# 09-General_I2C_Devices.net
KiCad netlist of a schematic drawn in Altium Designer
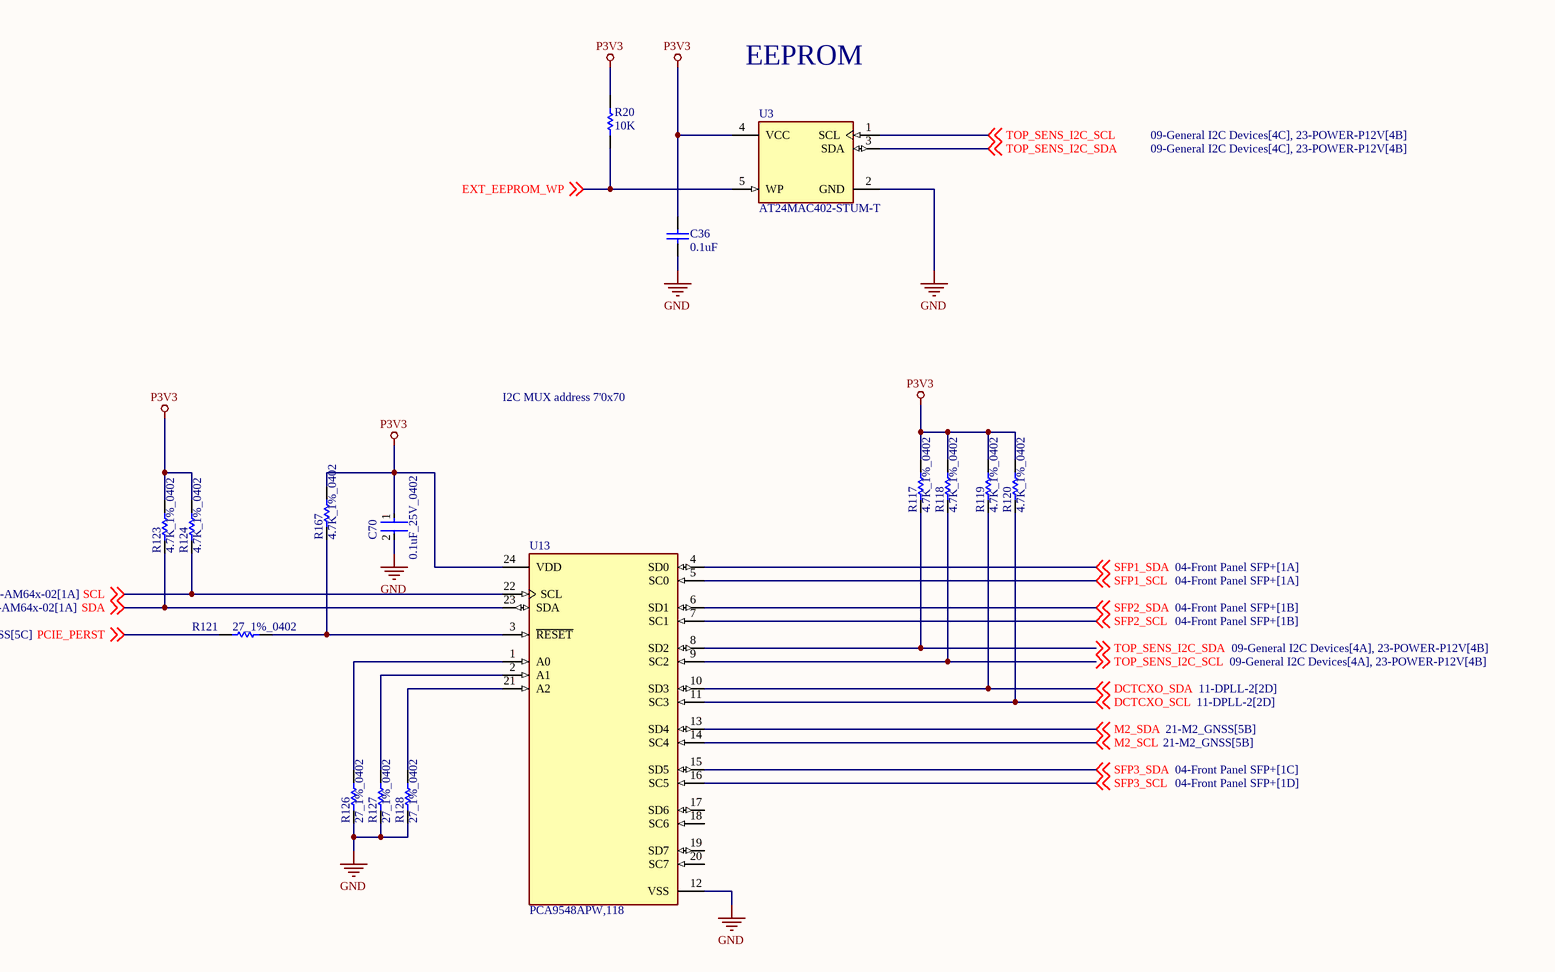
[diagram p0: 09-General I2C Devices.SchDoc]

(export (version "E")
  (design (tool "Eeschema 10.0.6"))
  (components
    (comp (ref "C36")
      (value "0.1uF")
      (footprint "CAPC1608X87X45ML20T05")
      (description "C0603X104K5RACAUTO")
      (fields (field (name "MANUFACTURER") "Kemet"))
      (libsource (lib "Altium Content Vault") (part "CAP"))
    )
    (comp (ref "C70")
      (value "0.1uF_25V_0402")
      (footprint "FP-0402-L_1_0_1-W_0_5_0_1-IPC_C")
      (description "General Purpose Ceramic Capacitor, 0402, 100nF, 10%, X7R, 15%, 25V")
      (fields (field (name "VOLTAGE") "25V") (field (name "TOLERANCE") "10%"))
      (libsource (lib "Altium Content Vault") (part "b4654b650e69147ec39a6b967a45e02"))
    )
    (comp (ref "R20")
      (value "10K")
      (footprint "RESC1608X55X30LL15T20")
      (fields (field (name "TOLERANCE") "±1%") (field (name "MANUFACTURER") "Stackpole-Electronics-Inc."))
      (libsource (lib "Altium Content Vault") (part "RES-2"))
    )
    (comp (ref "R117")
      (value "4.7K_1%_0402")
      (footprint "RESC1005X40X25NL10T10")
      (fields (field (name "MANUFACTURER") "Bourns") (field (name "PART NUMBER") "CR0402-FX-4701GLF"))
      (libsource (lib "Altium Content Vault") (part "RES"))
    )
    (comp (ref "R118")
      (value "4.7K_1%_0402")
      (footprint "RESC1005X40X25NL10T10")
      (fields (field (name "MANUFACTURER") "Bourns") (field (name "PART NUMBER") "CR0402-FX-4701GLF"))
      (libsource (lib "Altium Content Vault") (part "RES"))
    )
    (comp (ref "R119")
      (value "4.7K_1%_0402")
      (footprint "RESC1005X40X25NL10T10")
      (fields (field (name "MANUFACTURER") "Bourns") (field (name "PART NUMBER") "CR0402-FX-4701GLF"))
      (libsource (lib "Altium Content Vault") (part "RES"))
    )
    (comp (ref "R120")
      (value "4.7K_1%_0402")
      (footprint "RESC1005X40X25NL10T10")
      (fields (field (name "MANUFACTURER") "Bourns") (field (name "PART NUMBER") "CR0402-FX-4701GLF"))
      (libsource (lib "Altium Content Vault") (part "RES"))
    )
    (comp (ref "R121")
      (value "27_1%_0402")
      (footprint "RESC1005X40X25NL05T05")
      (fields (field (name "PART NUMBER") "CRCW040227R0FKED") (field (name "MANUFACTURER") "Vishay Dale"))
      (libsource (lib "Altium Content Vault") (part "RES"))
    )
    (comp (ref "R123")
      (value "4.7K_1%_0402")
      (footprint "RESC1005X40X25NL10T10")
      (fields (field (name "MANUFACTURER") "Bourns") (field (name "PART NUMBER") "CR0402-FX-4701GLF"))
      (libsource (lib "Altium Content Vault") (part "RES"))
    )
    (comp (ref "R124")
      (value "4.7K_1%_0402")
      (footprint "RESC1005X40X25NL10T10")
      (fields (field (name "MANUFACTURER") "Bourns") (field (name "PART NUMBER") "CR0402-FX-4701GLF"))
      (libsource (lib "Altium Content Vault") (part "RES"))
    )
    (comp (ref "R126")
      (value "27_1%_0402")
      (footprint "RESC1005X40X25NL05T05")
      (fields (field (name "PART NUMBER") "CRCW040227R0FKED") (field (name "MANUFACTURER") "Vishay Dale"))
      (libsource (lib "Altium Content Vault") (part "RES"))
    )
    (comp (ref "R127")
      (value "27_1%_0402")
      (footprint "RESC1005X40X25NL05T05")
      (fields (field (name "PART NUMBER") "CRCW040227R0FKED") (field (name "MANUFACTURER") "Vishay Dale"))
      (libsource (lib "Altium Content Vault") (part "RES"))
    )
    (comp (ref "R128")
      (value "27_1%_0402")
      (footprint "RESC1005X40X25NL05T05")
      (fields (field (name "PART NUMBER") "CRCW040227R0FKED") (field (name "MANUFACTURER") "Vishay Dale"))
      (libsource (lib "Altium Content Vault") (part "RES"))
    )
    (comp (ref "R167")
      (value "4.7K_1%_0402")
      (footprint "RESC1005X40X25NL10T10")
      (fields (field (name "MANUFACTURER") "Bourns") (field (name "PART NUMBER") "CR0402-FX-4701GLF"))
      (libsource (lib "Altium Content Vault") (part "RES"))
    )
    (comp (ref "U3")
      (value "AT24MAC402-STUM-T")
      (footprint "FP-5TS1-IPC_C")
      (description "IC EEPROM 2K I2C 1MHZ SOT23-5")
      (fields
        (field (name "MANUFACTURER") "Microchip")
        (field (name "OCTOPART") "https://octopart.com/at24mac402-stum-t-microchip-77758112")
      )
      (libsource (lib "Altium Content Vault") (part "93fe34f5f049140596bab6421a6454b"))
    )
    (comp (ref "U13")
      (value "PCA9548APW,118")
      (footprint "FP-SOT355-1-MFG")
      (description "IC INTERFACE SPECIALIZED 24TSSOP")
      (libsource (lib "Altium Content Vault") (part "3e168d29e2cae1e9eb34f21911d2ccb"))
    )
  )
  (nets
    (net (code "1") (name "DCTCXO_SCL") (class "Default")
      (node (ref "R120") (pin "1") (pinfunction "1_1") (pintype "passive"))
      (node (ref "U13") (pin "11") (pinfunction "SC3_11") (pintype "input"))
    )
    (net (code "2") (name "DCTCXO_SDA") (class "Default")
      (node (ref "R119") (pin "1") (pinfunction "1_1") (pintype "passive"))
      (node (ref "U13") (pin "10") (pinfunction "SD3_10") (pintype "bidirectional"))
    )
    (net (code "3") (name "EXT_EEPROM_WP") (class "Default")
      (node (ref "R20") (pin "1") (pinfunction "1_1") (pintype "passive"))
      (node (ref "U3") (pin "5") (pinfunction "WP_5") (pintype "input"))
    )
    (net (code "4") (name "GND") (class "Default")
      (node (ref "C36") (pin "1") (pinfunction "1_1") (pintype "passive"))
      (node (ref "C70") (pin "2") (pinfunction "2_2") (pintype "passive"))
      (node (ref "R126") (pin "1") (pinfunction "1_1") (pintype "passive"))
      (node (ref "R127") (pin "1") (pinfunction "1_1") (pintype "passive"))
      (node (ref "R128") (pin "1") (pinfunction "1_1") (pintype "passive"))
      (node (ref "U13") (pin "12") (pinfunction "VSS_12") (pintype "power_in"))
      (node (ref "U3") (pin "2") (pinfunction "GND_2") (pintype "power_in"))
    )
    (net (code "5") (name "M2_SCL") (class "Default")
      (node (ref "U13") (pin "14") (pinfunction "SC4_14") (pintype "input"))
    )
    (net (code "6") (name "M2_SDA") (class "Default")
      (node (ref "U13") (pin "13") (pinfunction "SD4_13") (pintype "bidirectional"))
    )
    (net (code "7") (name "Net-(U13-A0)") (class "Default")
      (node (ref "R126") (pin "2") (pinfunction "2_2") (pintype "passive"))
      (node (ref "U13") (pin "1") (pinfunction "A0_1") (pintype "input"))
    )
    (net (code "8") (name "Net-(U13-A1)") (class "Default")
      (node (ref "R127") (pin "2") (pinfunction "2_2") (pintype "passive"))
      (node (ref "U13") (pin "2") (pinfunction "A1_2") (pintype "input"))
    )
    (net (code "9") (name "Net-(U13-A2)") (class "Default")
      (node (ref "R128") (pin "2") (pinfunction "2_2") (pintype "passive"))
      (node (ref "U13") (pin "21") (pinfunction "A2_21") (pintype "input"))
    )
    (net (code "10") (name "Net-(U13-~{RESET})") (class "Default")
      (node (ref "R121") (pin "2") (pinfunction "2_2") (pintype "passive"))
      (node (ref "R167") (pin "1") (pinfunction "1_1") (pintype "passive"))
      (node (ref "U13") (pin "3") (pinfunction "~{RESET}_3") (pintype "input"))
    )
    (net (code "11") (name "P3V3") (class "Default")
      (node (ref "C36") (pin "2") (pinfunction "2_2") (pintype "passive"))
      (node (ref "C70") (pin "1") (pinfunction "1_1") (pintype "passive"))
      (node (ref "R117") (pin "2") (pinfunction "2_2") (pintype "passive"))
      (node (ref "R118") (pin "2") (pinfunction "2_2") (pintype "passive"))
      (node (ref "R119") (pin "2") (pinfunction "2_2") (pintype "passive"))
      (node (ref "R120") (pin "2") (pinfunction "2_2") (pintype "passive"))
      (node (ref "R123") (pin "2") (pinfunction "2_2") (pintype "passive"))
      (node (ref "R124") (pin "2") (pinfunction "2_2") (pintype "passive"))
      (node (ref "R167") (pin "2") (pinfunction "2_2") (pintype "passive"))
      (node (ref "R20") (pin "2") (pinfunction "2_2") (pintype "passive"))
      (node (ref "U13") (pin "24") (pinfunction "VDD_24") (pintype "power_in"))
      (node (ref "U3") (pin "4") (pinfunction "VCC_4") (pintype "power_in"))
    )
    (net (code "12") (name "PCIE_PERST") (class "Default")
      (node (ref "R121") (pin "1") (pinfunction "1_1") (pintype "passive"))
    )
    (net (code "13") (name "SCL") (class "Default")
      (node (ref "R124") (pin "1") (pinfunction "1_1") (pintype "passive"))
      (node (ref "U13") (pin "22") (pinfunction "SCL_22") (pintype "input"))
    )
    (net (code "14") (name "SDA") (class "Default")
      (node (ref "R123") (pin "1") (pinfunction "1_1") (pintype "passive"))
      (node (ref "U13") (pin "23") (pinfunction "SDA_23") (pintype "bidirectional"))
    )
    (net (code "15") (name "SFP1_SCL") (class "Default")
      (node (ref "U13") (pin "5") (pinfunction "SC0_5") (pintype "input"))
    )
    (net (code "16") (name "SFP1_SDA") (class "Default")
      (node (ref "U13") (pin "4") (pinfunction "SD0_4") (pintype "bidirectional"))
    )
    (net (code "17") (name "SFP2_SCL") (class "Default")
      (node (ref "U13") (pin "7") (pinfunction "SC1_7") (pintype "input"))
    )
    (net (code "18") (name "SFP2_SDA") (class "Default")
      (node (ref "U13") (pin "6") (pinfunction "SD1_6") (pintype "bidirectional"))
    )
    (net (code "19") (name "SFP3_SCL") (class "Default")
      (node (ref "U13") (pin "16") (pinfunction "SC5_16") (pintype "input"))
    )
    (net (code "20") (name "SFP3_SDA") (class "Default")
      (node (ref "U13") (pin "15") (pinfunction "SD5_15") (pintype "bidirectional"))
    )
    (net (code "21") (name "TOP_SENS_I2C_SCL") (class "Default")
      (node (ref "R118") (pin "1") (pinfunction "1_1") (pintype "passive"))
      (node (ref "U13") (pin "9") (pinfunction "SC2_9") (pintype "input"))
      (node (ref "U3") (pin "1") (pinfunction "SCL_1") (pintype "input"))
    )
    (net (code "22") (name "TOP_SENS_I2C_SDA") (class "Default")
      (node (ref "R117") (pin "1") (pinfunction "1_1") (pintype "passive"))
      (node (ref "U13") (pin "8") (pinfunction "SD2_8") (pintype "bidirectional"))
      (node (ref "U3") (pin "3") (pinfunction "SDA_3") (pintype "bidirectional"))
    )
    (net (code "23") (name "unconnected-(U13-SC6-Pad18)") (class "Default")
      (node (ref "U13") (pin "18") (pinfunction "SC6_18") (pintype "input"))
    )
    (net (code "24") (name "unconnected-(U13-SC7-Pad20)") (class "Default")
      (node (ref "U13") (pin "20") (pinfunction "SC7_20") (pintype "input"))
    )
    (net (code "25") (name "unconnected-(U13-SD6-Pad17)") (class "Default")
      (node (ref "U13") (pin "17") (pinfunction "SD6_17") (pintype "bidirectional"))
    )
    (net (code "26") (name "unconnected-(U13-SD7-Pad19)") (class "Default")
      (node (ref "U13") (pin "19") (pinfunction "SD7_19") (pintype "bidirectional"))
    )
  )
)
